# summing_circuit.net
KiCad netlist of a schematic drawn in Altium Designer
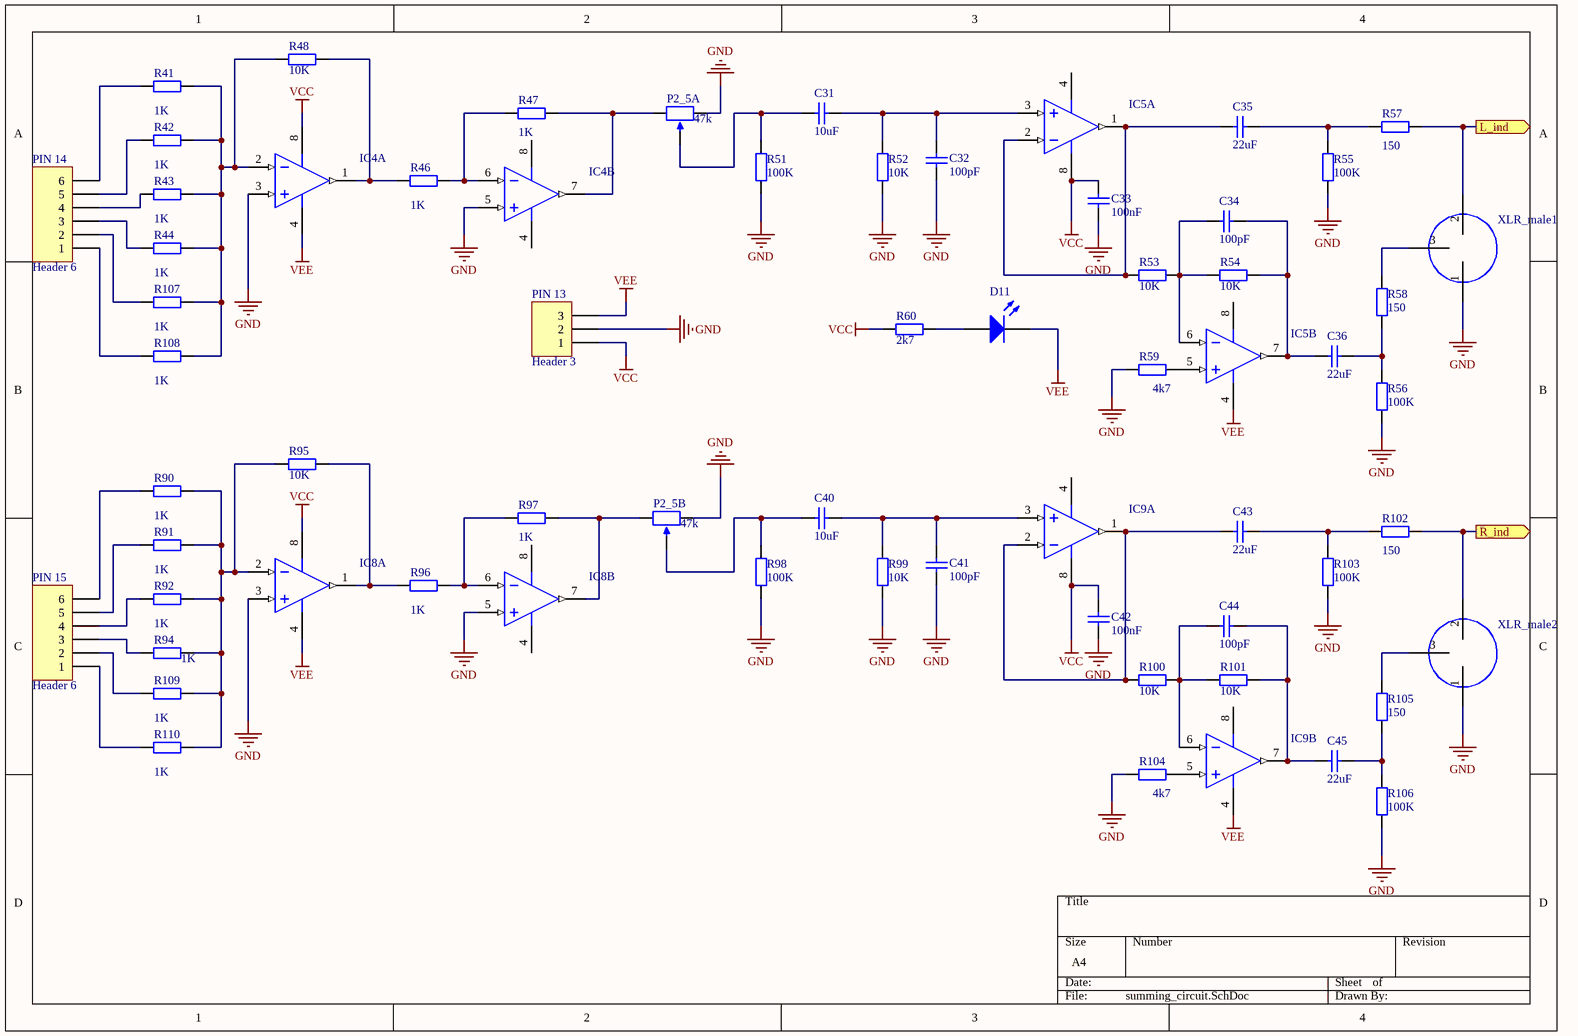
[diagram p0: summing_circuit.SchDoc]

(export (version "E")
  (design (tool "Eeschema 10.0.6"))
  (components
    (comp (ref "C31")
      (value "10uF")
      (footprint "Capacitor 10uF")
      (description "Capacitor")
      (fields (field (name "Comment") "Cap") (field (name "PUBLISHER") "Altium Limited"))
      (libsource (lib "Autio_Mixer") (part "Cap"))
    )
    (comp (ref "C32")
      (value "100pF")
      (footprint "Capacitor 100pF")
      (description "Capacitor")
      (fields (field (name "Comment") "Cap") (field (name "PUBLISHER") "Altium Limited"))
      (libsource (lib "Autio_Mixer") (part "Cap"))
    )
    (comp (ref "C33")
      (value "100nF")
      (footprint "Capacitor 22nF, 47nF, 100nF")
      (description "Capacitor")
      (fields (field (name "Comment") "Cap") (field (name "PUBLISHER") "Altium Limited"))
      (libsource (lib "Autio_Mixer") (part "Cap_3"))
    )
    (comp (ref "C34")
      (value "100pF")
      (footprint "Capacitor 100pF")
      (description "Capacitor")
      (fields (field (name "Comment") "Cap") (field (name "PUBLISHER") "Altium Limited"))
      (libsource (lib "Autio_Mixer") (part "Cap"))
    )
    (comp (ref "C35")
      (value "22uF")
      (footprint "Capacitor 100uF")
      (description "Capacitor")
      (fields (field (name "Comment") "Cap") (field (name "PUBLISHER") "Altium Limited"))
      (libsource (lib "Autio_Mixer") (part "Cap"))
    )
    (comp (ref "C36")
      (value "22uF")
      (footprint "Capacitor 100uF")
      (description "Capacitor")
      (fields (field (name "Comment") "Cap") (field (name "PUBLISHER") "Altium Limited"))
      (libsource (lib "Autio_Mixer") (part "Cap_5"))
    )
    (comp (ref "C40")
      (value "10uF")
      (footprint "Capacitor 10uF")
      (description "Capacitor")
      (fields (field (name "Comment") "Cap") (field (name "PUBLISHER") "Altium Limited"))
      (libsource (lib "Autio_Mixer") (part "Cap"))
    )
    (comp (ref "C41")
      (value "100pF")
      (footprint "Capacitor 100pF")
      (description "Capacitor")
      (fields (field (name "Comment") "Cap") (field (name "PUBLISHER") "Altium Limited"))
      (libsource (lib "Autio_Mixer") (part "Cap"))
    )
    (comp (ref "C42")
      (value "100nF")
      (footprint "Capacitor 22nF, 47nF, 100nF")
      (description "Capacitor")
      (fields (field (name "Comment") "Cap") (field (name "PUBLISHER") "Altium Limited"))
      (libsource (lib "Autio_Mixer") (part "Cap_3"))
    )
    (comp (ref "C43")
      (value "22uF")
      (footprint "Capacitor 100pF")
      (description "Capacitor")
      (fields (field (name "Comment") "Cap") (field (name "PUBLISHER") "Altium Limited"))
      (libsource (lib "Autio_Mixer") (part "Cap"))
    )
    (comp (ref "C44")
      (value "100pF")
      (footprint "Capacitor 100uF")
      (description "Capacitor")
      (fields (field (name "Comment") "Cap") (field (name "PUBLISHER") "Altium Limited"))
      (libsource (lib "Autio_Mixer") (part "Cap"))
    )
    (comp (ref "C45")
      (value "22uF")
      (footprint "Capacitor 100uF")
      (description "Capacitor")
      (fields (field (name "Comment") "Cap") (field (name "PUBLISHER") "Altium Limited"))
      (libsource (lib "Autio_Mixer") (part "Cap_5"))
    )
    (comp (ref "D11")
      (value "LED1")
      (footprint "LED")
      (description "Typical RED GaAs LED")
      (fields (field (name "PUBLISHER") "Altium Limited"))
      (libsource (lib "Autio_Mixer") (part "LED1"))
    )
    (comp (ref "IC4")
      (value "LM833DR2G")
      (footprint "OPAMP_LM833")
      (description "Low Noise, Audio Dual Operational Amplifier, -40 to 85 degC, 8-Pin SOIC, Pb-Free, Tape and Reel")
      (fields (field (name "MANUFACTURER") "On Semiconductor"))
      (libsource (lib "Autio_Mixer") (part "opamp_LM833"))
    )
    (comp (ref "IC5")
      (value "LM833DR2G")
      (footprint "OPAMP_LM833")
      (description "Low Noise, Audio Dual Operational Amplifier, -40 to 85 degC, 8-Pin SOIC, Pb-Free, Tape and Reel")
      (fields (field (name "MANUFACTURER") "On Semiconductor"))
      (libsource (lib "Autio_Mixer") (part "opamp_LM833"))
    )
    (comp (ref "IC8")
      (value "LM833DR2G")
      (footprint "OPAMP_LM833")
      (description "Low Noise, Audio Dual Operational Amplifier, -40 to 85 degC, 8-Pin SOIC, Pb-Free, Tape and Reel")
      (fields (field (name "MANUFACTURER") "On Semiconductor"))
      (libsource (lib "Autio_Mixer") (part "opamp_LM833"))
    )
    (comp (ref "IC9")
      (value "LM833DR2G")
      (footprint "OPAMP_LM833")
      (description "Low Noise, Audio Dual Operational Amplifier, -40 to 85 degC, 8-Pin SOIC, Pb-Free, Tape and Reel")
      (fields (field (name "MANUFACTURER") "On Semiconductor"))
      (libsource (lib "Autio_Mixer") (part "opamp_LM833"))
    )
    (comp (ref "P2_5A")
      (value "47k")
      (footprint "header_3")
      (description "Potentiometer")
      (fields (field (name "Comment") "RPot") (field (name "PUBLISHER") "Altium Limited"))
      (libsource (lib "Autio_Mixer") (part "RPot"))
    )
    (comp (ref "P2_5B")
      (value "47k")
      (footprint "header_3")
      (description "Potentiometer")
      (fields (field (name "Comment") "RPot") (field (name "PUBLISHER") "Altium Limited"))
      (libsource (lib "Autio_Mixer") (part "RPot"))
    )
    (comp (ref "PIN 13")
      (value "Header 3")
      (footprint "header_3")
      (description "Header, 3-Pin")
      (fields (field (name "PUBLISHER") "Altium Limited"))
      (libsource (lib "Miscellaneous Connectors") (part "Header 3"))
    )
    (comp (ref "PIN 14")
      (value "Header 6")
      (footprint "header_6")
      (description "Header, 6-Pin")
      (fields (field (name "PUBLISHER") "Altium Limited"))
      (libsource (lib "Miscellaneous Connectors") (part "Header 6"))
    )
    (comp (ref "PIN 15")
      (value "Header 6")
      (footprint "header_6")
      (description "Header, 6-Pin")
      (fields (field (name "PUBLISHER") "Altium Limited"))
      (libsource (lib "Miscellaneous Connectors") (part "Header 6"))
    )
    (comp (ref "R41")
      (value "1K")
      (footprint "C1206")
      (description "Resistor")
      (fields (field (name "Comment") "Res2") (field (name "PUBLISHER") "Altium Limited"))
      (libsource (lib "Miscellaneous Devices") (part "Res2"))
    )
    (comp (ref "R42")
      (value "1K")
      (footprint "C1206")
      (description "Resistor")
      (fields (field (name "Comment") "Res2") (field (name "PUBLISHER") "Altium Limited"))
      (libsource (lib "Miscellaneous Devices") (part "Res2"))
    )
    (comp (ref "R43")
      (value "1K")
      (footprint "C1206")
      (description "Resistor")
      (fields (field (name "Comment") "Res2") (field (name "PUBLISHER") "Altium Limited"))
      (libsource (lib "Miscellaneous Devices") (part "Res2"))
    )
    (comp (ref "R44")
      (value "1K")
      (footprint "C1206")
      (description "Resistor")
      (fields (field (name "Comment") "Res2") (field (name "PUBLISHER") "Altium Limited"))
      (libsource (lib "Miscellaneous Devices") (part "Res2"))
    )
    (comp (ref "R46")
      (value "1K")
      (footprint "C1206")
      (description "Resistor")
      (fields (field (name "Comment") "Res2") (field (name "PUBLISHER") "Altium Limited"))
      (libsource (lib "Miscellaneous Devices") (part "Res2"))
    )
    (comp (ref "R47")
      (value "1K")
      (footprint "C1206")
      (description "Resistor")
      (fields (field (name "Comment") "Res2") (field (name "PUBLISHER") "Altium Limited"))
      (libsource (lib "Miscellaneous Devices") (part "Res2"))
    )
    (comp (ref "R48")
      (value "10K")
      (footprint "C1206")
      (description "Resistor")
      (fields (field (name "Comment") "Res2") (field (name "PUBLISHER") "Altium Limited"))
      (libsource (lib "Autio_Mixer") (part "Res2_3"))
    )
    (comp (ref "R51")
      (value "100K")
      (footprint "C1206")
      (description "Resistor")
      (fields (field (name "Comment") "Res2") (field (name "PUBLISHER") "Altium Limited"))
      (libsource (lib "Autio_Mixer") (part "Res2_5"))
    )
    (comp (ref "R52")
      (value "10K")
      (footprint "C1206")
      (description "Resistor")
      (fields (field (name "Comment") "Res2") (field (name "PUBLISHER") "Altium Limited"))
      (libsource (lib "") (part "Res2_3_1"))
    )
    (comp (ref "R53")
      (value "10K")
      (footprint "C1206")
      (description "Resistor")
      (fields (field (name "Comment") "Res2") (field (name "PUBLISHER") "Altium Limited"))
      (libsource (lib "Autio_Mixer") (part "Res2_3"))
    )
    (comp (ref "R54")
      (value "10K")
      (footprint "C1206")
      (description "Resistor")
      (fields (field (name "Comment") "Res2") (field (name "PUBLISHER") "Altium Limited"))
      (libsource (lib "Autio_Mixer") (part "Res2_3"))
    )
    (comp (ref "R55")
      (value "100K")
      (footprint "C1206")
      (description "Resistor")
      (fields (field (name "Comment") "Res2") (field (name "PUBLISHER") "Altium Limited"))
      (libsource (lib "Autio_Mixer") (part "Res2_5"))
    )
    (comp (ref "R56")
      (value "100K")
      (footprint "C1206")
      (description "Resistor")
      (fields (field (name "Comment") "Res2") (field (name "PUBLISHER") "Altium Limited"))
      (libsource (lib "Autio_Mixer") (part "Res2_5"))
    )
    (comp (ref "R57")
      (value "150")
      (footprint "C1206")
      (description "Resistor")
      (fields (field (name "Comment") "Res2") (field (name "PUBLISHER") "Altium Limited"))
      (libsource (lib "Miscellaneous Devices") (part "Res2"))
    )
    (comp (ref "R58")
      (value "150")
      (footprint "C1206")
      (description "Resistor")
      (fields (field (name "Comment") "Res2") (field (name "PUBLISHER") "Altium Limited"))
      (libsource (lib "") (part "Res2_1"))
    )
    (comp (ref "R59")
      (value "4k7")
      (footprint "C1206")
      (description "Resistor")
      (fields (field (name "Comment") "Res2") (field (name "PUBLISHER") "Altium Limited"))
      (libsource (lib "Miscellaneous Devices") (part "Res2"))
    )
    (comp (ref "R60")
      (value "2k7")
      (footprint "C1206")
      (description "Resistor")
      (fields (field (name "Comment") "Res2") (field (name "PUBLISHER") "Altium Limited"))
      (libsource (lib "Autio_Mixer") (part "Res_16"))
    )
    (comp (ref "R90")
      (value "1K")
      (footprint "C1206")
      (description "Resistor")
      (fields (field (name "Comment") "Res2") (field (name "PUBLISHER") "Altium Limited"))
      (libsource (lib "Miscellaneous Devices") (part "Res2"))
    )
    (comp (ref "R91")
      (value "1K")
      (footprint "C1206")
      (description "Resistor")
      (fields (field (name "Comment") "Res2") (field (name "PUBLISHER") "Altium Limited"))
      (libsource (lib "Miscellaneous Devices") (part "Res2"))
    )
    (comp (ref "R92")
      (value "1K")
      (footprint "C1206")
      (description "Resistor")
      (fields (field (name "Comment") "Res2") (field (name "PUBLISHER") "Altium Limited"))
      (libsource (lib "Miscellaneous Devices") (part "Res2"))
    )
    (comp (ref "R94")
      (value "1K")
      (footprint "C1206")
      (description "Resistor")
      (fields (field (name "Comment") "Res2") (field (name "PUBLISHER") "Altium Limited"))
      (libsource (lib "Miscellaneous Devices") (part "Res2"))
    )
    (comp (ref "R95")
      (value "10K")
      (footprint "C1206")
      (description "Resistor")
      (fields (field (name "Comment") "Res2") (field (name "PUBLISHER") "Altium Limited"))
      (libsource (lib "Autio_Mixer") (part "Res2_3"))
    )
    (comp (ref "R96")
      (value "1K")
      (footprint "C1206")
      (description "Resistor")
      (fields (field (name "Comment") "Res2") (field (name "PUBLISHER") "Altium Limited"))
      (libsource (lib "Miscellaneous Devices") (part "Res2"))
    )
    (comp (ref "R97")
      (value "1K")
      (footprint "C1206")
      (description "Resistor")
      (fields (field (name "Comment") "Res2") (field (name "PUBLISHER") "Altium Limited"))
      (libsource (lib "Miscellaneous Devices") (part "Res2"))
    )
    (comp (ref "R98")
      (value "100K")
      (footprint "C1206")
      (description "Resistor")
      (fields (field (name "Comment") "Res2") (field (name "PUBLISHER") "Altium Limited"))
      (libsource (lib "Autio_Mixer") (part "Res2_5"))
    )
    (comp (ref "R99")
      (value "10K")
      (footprint "C1206")
      (description "Resistor")
      (fields (field (name "Comment") "Res2") (field (name "PUBLISHER") "Altium Limited"))
      (libsource (lib "") (part "Res2_3_1"))
    )
    (comp (ref "R100")
      (value "10K")
      (footprint "C1206")
      (description "Resistor")
      (fields (field (name "Comment") "Res2") (field (name "PUBLISHER") "Altium Limited"))
      (libsource (lib "Autio_Mixer") (part "Res2_3"))
    )
    (comp (ref "R101")
      (value "10K")
      (footprint "C1206")
      (description "Resistor")
      (fields (field (name "Comment") "Res2") (field (name "PUBLISHER") "Altium Limited"))
      (libsource (lib "Autio_Mixer") (part "Res2_3"))
    )
    (comp (ref "R102")
      (value "150")
      (footprint "C1206")
      (description "Resistor")
      (fields (field (name "Comment") "Res2") (field (name "PUBLISHER") "Altium Limited"))
      (libsource (lib "Miscellaneous Devices") (part "Res2"))
    )
    (comp (ref "R103")
      (value "100K")
      (footprint "C1206")
      (description "Resistor")
      (fields (field (name "Comment") "Res2") (field (name "PUBLISHER") "Altium Limited"))
      (libsource (lib "Autio_Mixer") (part "Res2_5"))
    )
    (comp (ref "R104")
      (value "4k7")
      (footprint "C1206")
      (description "Resistor")
      (fields (field (name "Comment") "Res2") (field (name "PUBLISHER") "Altium Limited"))
      (libsource (lib "Miscellaneous Devices") (part "Res2"))
    )
    (comp (ref "R105")
      (value "150")
      (footprint "C1206")
      (description "Resistor")
      (fields (field (name "Comment") "Res2") (field (name "PUBLISHER") "Altium Limited"))
      (libsource (lib "") (part "Res2_1"))
    )
    (comp (ref "R106")
      (value "100K")
      (footprint "C1206")
      (description "Resistor")
      (fields (field (name "Comment") "Res2") (field (name "PUBLISHER") "Altium Limited"))
      (libsource (lib "Autio_Mixer") (part "Res2_5"))
    )
    (comp (ref "R107")
      (value "1K")
      (footprint "C1206")
      (description "Resistor")
      (fields (field (name "Comment") "Res2") (field (name "PUBLISHER") "Altium Limited"))
      (libsource (lib "Miscellaneous Devices") (part "Res2"))
    )
    (comp (ref "R108")
      (value "1K")
      (footprint "C1206")
      (description "Resistor")
      (fields (field (name "Comment") "Res2") (field (name "PUBLISHER") "Altium Limited"))
      (libsource (lib "Miscellaneous Devices") (part "Res2"))
    )
    (comp (ref "R109")
      (value "1K")
      (footprint "C1206")
      (description "Resistor")
      (fields (field (name "Comment") "Res2") (field (name "PUBLISHER") "Altium Limited"))
      (libsource (lib "Miscellaneous Devices") (part "Res2"))
    )
    (comp (ref "R110")
      (value "1K")
      (footprint "C1206")
      (description "Resistor")
      (fields (field (name "Comment") "Res2") (field (name "PUBLISHER") "Altium Limited"))
      (libsource (lib "Miscellaneous Devices") (part "Res2"))
    )
    (comp (ref "XLR_male1")
      (value "XLR_male")
      (footprint "XLR_MALE_Neutrik_NC3_MAV")
      (libsource (lib "Autio_Mixer") (part "XLR_male"))
    )
    (comp (ref "XLR_male2")
      (value "XLR_male")
      (footprint "XLR_MALE_Neutrik_NC3_MAV")
      (libsource (lib "Autio_Mixer") (part "XLR_male"))
    )
  )
  (nets
    (net (code "1") (name "/L_ind") (class "Default")
      (node (ref "R57") (pin "2") (pinfunction "2_2") (pintype "passive"))
      (node (ref "XLR_male1") (pin "2") (pinfunction "Pos_2") (pintype "passive"))
    )
    (net (code "2") (name "/R_ind") (class "Default")
      (node (ref "R102") (pin "2") (pinfunction "2_2") (pintype "passive"))
      (node (ref "XLR_male2") (pin "2") (pinfunction "Pos_2") (pintype "passive"))
    )
    (net (code "3") (name "GND") (class "Default")
      (node (ref "C32") (pin "1") (pinfunction "1_1") (pintype "passive"))
      (node (ref "C33") (pin "1") (pinfunction "1_1") (pintype "passive"))
      (node (ref "C41") (pin "1") (pinfunction "1_1") (pintype "passive"))
      (node (ref "C42") (pin "1") (pinfunction "1_1") (pintype "passive"))
      (node (ref "IC4") (pin "3") (pinfunction "IN1+_3") (pintype "input"))
      (node (ref "IC4") (pin "5") (pinfunction "IN2+_5") (pintype "input"))
      (node (ref "IC8") (pin "3") (pinfunction "IN1+_3") (pintype "input"))
      (node (ref "IC8") (pin "5") (pinfunction "IN2+_5") (pintype "input"))
      (node (ref "P2_5A") (pin "3") (pinfunction "BOT_3") (pintype "passive"))
      (node (ref "P2_5B") (pin "3") (pinfunction "BOT_3") (pintype "passive"))
      (node (ref "PIN 13") (pin "1") (pinfunction "2_1") (pintype "passive"))
      (node (ref "R103") (pin "1") (pinfunction "1_1") (pintype "passive"))
      (node (ref "R104") (pin "1") (pinfunction "1_1") (pintype "passive"))
      (node (ref "R106") (pin "1") (pinfunction "1_1") (pintype "passive"))
      (node (ref "R51") (pin "1") (pinfunction "1_1") (pintype "passive"))
      (node (ref "R52") (pin "1") (pinfunction "1_1") (pintype "passive"))
      (node (ref "R55") (pin "1") (pinfunction "1_1") (pintype "passive"))
      (node (ref "R56") (pin "1") (pinfunction "1_1") (pintype "passive"))
      (node (ref "R59") (pin "1") (pinfunction "1_1") (pintype "passive"))
      (node (ref "R98") (pin "1") (pinfunction "1_1") (pintype "passive"))
      (node (ref "R99") (pin "1") (pinfunction "1_1") (pintype "passive"))
      (node (ref "XLR_male1") (pin "1") (pinfunction "GND_1") (pintype "passive"))
      (node (ref "XLR_male2") (pin "1") (pinfunction "GND_1") (pintype "passive"))
    )
    (net (code "4") (name "Net-(C35-Pad2)") (class "Default")
      (node (ref "C35") (pin "2") (pinfunction "2_2") (pintype "passive"))
      (node (ref "R55") (pin "2") (pinfunction "2_2") (pintype "passive"))
      (node (ref "R57") (pin "1") (pinfunction "1_1") (pintype "passive"))
    )
    (net (code "5") (name "Net-(C36-Pad2)") (class "Default")
      (node (ref "C36") (pin "2") (pinfunction "2_2") (pintype "passive"))
      (node (ref "R56") (pin "2") (pinfunction "2_2") (pintype "passive"))
      (node (ref "R58") (pin "1") (pinfunction "1_1") (pintype "passive"))
    )
    (net (code "6") (name "Net-(C43-Pad2)") (class "Default")
      (node (ref "C43") (pin "2") (pinfunction "2_2") (pintype "passive"))
      (node (ref "R102") (pin "1") (pinfunction "1_1") (pintype "passive"))
      (node (ref "R103") (pin "2") (pinfunction "2_2") (pintype "passive"))
    )
    (net (code "7") (name "Net-(C45-Pad2)") (class "Default")
      (node (ref "C45") (pin "2") (pinfunction "2_2") (pintype "passive"))
      (node (ref "R105") (pin "1") (pinfunction "1_1") (pintype "passive"))
      (node (ref "R106") (pin "2") (pinfunction "2_2") (pintype "passive"))
    )
    (net (code "8") (name "Net-(D11-A)") (class "Default")
      (node (ref "D11") (pin "1") (pinfunction "A_1") (pintype "passive"))
      (node (ref "R60") (pin "2") (pinfunction "2_2") (pintype "passive"))
    )
    (net (code "9") (name "Net-(IC4A-IN1-)") (class "Default")
      (node (ref "IC4") (pin "2") (pinfunction "IN1-_2") (pintype "input"))
      (node (ref "R107") (pin "2") (pinfunction "2_2") (pintype "passive"))
      (node (ref "R108") (pin "2") (pinfunction "2_2") (pintype "passive"))
      (node (ref "R41") (pin "2") (pinfunction "2_2") (pintype "passive"))
      (node (ref "R42") (pin "2") (pinfunction "2_2") (pintype "passive"))
      (node (ref "R43") (pin "2") (pinfunction "2_2") (pintype "passive"))
      (node (ref "R44") (pin "2") (pinfunction "2_2") (pintype "passive"))
      (node (ref "R48") (pin "1") (pinfunction "1_1") (pintype "passive"))
    )
    (net (code "10") (name "Net-(IC4A-OUT1)") (class "Default")
      (node (ref "IC4") (pin "1") (pinfunction "OUT1_1") (pintype "output"))
      (node (ref "R46") (pin "1") (pinfunction "1_1") (pintype "passive"))
      (node (ref "R48") (pin "2") (pinfunction "2_2") (pintype "passive"))
    )
    (net (code "11") (name "Net-(IC4B-IN2-)") (class "Default")
      (node (ref "IC4") (pin "6") (pinfunction "IN2-_6") (pintype "input"))
      (node (ref "R46") (pin "2") (pinfunction "2_2") (pintype "passive"))
      (node (ref "R47") (pin "1") (pinfunction "1_1") (pintype "passive"))
    )
    (net (code "12") (name "Net-(IC4B-OUT2)") (class "Default")
      (node (ref "IC4") (pin "7") (pinfunction "OUT2_7") (pintype "output"))
      (node (ref "P2_5A") (pin "1") (pinfunction "TOP_1") (pintype "passive"))
      (node (ref "R47") (pin "2") (pinfunction "2_2") (pintype "passive"))
    )
    (net (code "13") (name "Net-(IC5A-IN1+)") (class "Default")
      (node (ref "C31") (pin "2") (pinfunction "2_2") (pintype "passive"))
      (node (ref "C32") (pin "2") (pinfunction "2_2") (pintype "passive"))
      (node (ref "IC5") (pin "3") (pinfunction "IN1+_3") (pintype "input"))
      (node (ref "R52") (pin "2") (pinfunction "2_2") (pintype "passive"))
    )
    (net (code "14") (name "Net-(IC5A-IN1-)") (class "Default")
      (node (ref "C35") (pin "1") (pinfunction "1_1") (pintype "passive"))
      (node (ref "IC5") (pin "1") (pinfunction "OUT1_1") (pintype "output"))
      (node (ref "IC5") (pin "2") (pinfunction "IN1-_2") (pintype "input"))
      (node (ref "R53") (pin "1") (pinfunction "1_1") (pintype "passive"))
    )
    (net (code "15") (name "Net-(IC5B-IN2+)") (class "Default")
      (node (ref "IC5") (pin "5") (pinfunction "IN2+_5") (pintype "input"))
      (node (ref "R59") (pin "2") (pinfunction "2_2") (pintype "passive"))
    )
    (net (code "16") (name "Net-(IC5B-IN2-)") (class "Default")
      (node (ref "C34") (pin "1") (pinfunction "1_1") (pintype "passive"))
      (node (ref "IC5") (pin "6") (pinfunction "IN2-_6") (pintype "input"))
      (node (ref "R53") (pin "2") (pinfunction "2_2") (pintype "passive"))
      (node (ref "R54") (pin "1") (pinfunction "1_1") (pintype "passive"))
    )
    (net (code "17") (name "Net-(IC5B-OUT2)") (class "Default")
      (node (ref "C34") (pin "2") (pinfunction "2_2") (pintype "passive"))
      (node (ref "C36") (pin "1") (pinfunction "1_1") (pintype "passive"))
      (node (ref "IC5") (pin "7") (pinfunction "OUT2_7") (pintype "output"))
      (node (ref "R54") (pin "2") (pinfunction "2_2") (pintype "passive"))
    )
    (net (code "18") (name "Net-(IC8A-IN1-)") (class "Default")
      (node (ref "IC8") (pin "2") (pinfunction "IN1-_2") (pintype "input"))
      (node (ref "R109") (pin "2") (pinfunction "2_2") (pintype "passive"))
      (node (ref "R110") (pin "2") (pinfunction "2_2") (pintype "passive"))
      (node (ref "R90") (pin "2") (pinfunction "2_2") (pintype "passive"))
      (node (ref "R91") (pin "2") (pinfunction "2_2") (pintype "passive"))
      (node (ref "R92") (pin "2") (pinfunction "2_2") (pintype "passive"))
      (node (ref "R94") (pin "2") (pinfunction "2_2") (pintype "passive"))
      (node (ref "R95") (pin "1") (pinfunction "1_1") (pintype "passive"))
    )
    (net (code "19") (name "Net-(IC8A-OUT1)") (class "Default")
      (node (ref "IC8") (pin "1") (pinfunction "OUT1_1") (pintype "output"))
      (node (ref "R95") (pin "2") (pinfunction "2_2") (pintype "passive"))
      (node (ref "R96") (pin "1") (pinfunction "1_1") (pintype "passive"))
    )
    (net (code "20") (name "Net-(IC8B-IN2-)") (class "Default")
      (node (ref "IC8") (pin "6") (pinfunction "IN2-_6") (pintype "input"))
      (node (ref "R96") (pin "2") (pinfunction "2_2") (pintype "passive"))
      (node (ref "R97") (pin "1") (pinfunction "1_1") (pintype "passive"))
    )
    (net (code "21") (name "Net-(IC8B-OUT2)") (class "Default")
      (node (ref "IC8") (pin "7") (pinfunction "OUT2_7") (pintype "output"))
      (node (ref "P2_5B") (pin "1") (pinfunction "TOP_1") (pintype "passive"))
      (node (ref "R97") (pin "2") (pinfunction "2_2") (pintype "passive"))
    )
    (net (code "22") (name "Net-(IC9A-IN1+)") (class "Default")
      (node (ref "C40") (pin "2") (pinfunction "2_2") (pintype "passive"))
      (node (ref "C41") (pin "2") (pinfunction "2_2") (pintype "passive"))
      (node (ref "IC9") (pin "3") (pinfunction "IN1+_3") (pintype "input"))
      (node (ref "R99") (pin "2") (pinfunction "2_2") (pintype "passive"))
    )
    (net (code "23") (name "Net-(IC9A-IN1-)") (class "Default")
      (node (ref "C43") (pin "1") (pinfunction "1_1") (pintype "passive"))
      (node (ref "IC9") (pin "1") (pinfunction "OUT1_1") (pintype "output"))
      (node (ref "IC9") (pin "2") (pinfunction "IN1-_2") (pintype "input"))
      (node (ref "R100") (pin "1") (pinfunction "1_1") (pintype "passive"))
    )
    (net (code "24") (name "Net-(IC9B-IN2+)") (class "Default")
      (node (ref "IC9") (pin "5") (pinfunction "IN2+_5") (pintype "input"))
      (node (ref "R104") (pin "2") (pinfunction "2_2") (pintype "passive"))
    )
    (net (code "25") (name "Net-(IC9B-IN2-)") (class "Default")
      (node (ref "C44") (pin "1") (pinfunction "1_1") (pintype "passive"))
      (node (ref "IC9") (pin "6") (pinfunction "IN2-_6") (pintype "input"))
      (node (ref "R100") (pin "2") (pinfunction "2_2") (pintype "passive"))
      (node (ref "R101") (pin "1") (pinfunction "1_1") (pintype "passive"))
    )
    (net (code "26") (name "Net-(IC9B-OUT2)") (class "Default")
      (node (ref "C44") (pin "2") (pinfunction "2_2") (pintype "passive"))
      (node (ref "C45") (pin "1") (pinfunction "1_1") (pintype "passive"))
      (node (ref "IC9") (pin "7") (pinfunction "OUT2_7") (pintype "output"))
      (node (ref "R101") (pin "2") (pinfunction "2_2") (pintype "passive"))
    )
    (net (code "27") (name "Net-(P2_5A-TAP)") (class "Default")
      (node (ref "C31") (pin "1") (pinfunction "1_1") (pintype "passive"))
      (node (ref "P2_5A") (pin "2") (pinfunction "TAP_2") (pintype "passive"))
      (node (ref "R51") (pin "2") (pinfunction "2_2") (pintype "passive"))
    )
    (net (code "28") (name "Net-(P2_5B-TAP)") (class "Default")
      (node (ref "C40") (pin "1") (pinfunction "1_1") (pintype "passive"))
      (node (ref "P2_5B") (pin "2") (pinfunction "TAP_2") (pintype "passive"))
      (node (ref "R98") (pin "2") (pinfunction "2_2") (pintype "passive"))
    )
    (net (code "29") (name "Net-(PIN 14-1)") (class "Default")
      (node (ref "PIN 14") (pin "2") (pinfunction "1_2") (pintype "passive"))
      (node (ref "R108") (pin "1") (pinfunction "1_1") (pintype "passive"))
    )
    (net (code "30") (name "Net-(PIN 14-2)") (class "Default")
      (node (ref "PIN 14") (pin "1") (pinfunction "2_1") (pintype "passive"))
      (node (ref "R107") (pin "1") (pinfunction "1_1") (pintype "passive"))
    )
    (net (code "31") (name "Net-(PIN 14-Pad3)") (class "Default")
      (node (ref "PIN 14") (pin "3") (pinfunction "3_3") (pintype "passive"))
      (node (ref "R44") (pin "1") (pinfunction "1_1") (pintype "passive"))
    )
    (net (code "32") (name "Net-(PIN 14-Pad4)") (class "Default")
      (node (ref "PIN 14") (pin "4") (pinfunction "4_4") (pintype "passive"))
      (node (ref "R43") (pin "1") (pinfunction "1_1") (pintype "passive"))
    )
    (net (code "33") (name "Net-(PIN 14-Pad5)") (class "Default")
      (node (ref "PIN 14") (pin "5") (pinfunction "5_5") (pintype "passive"))
      (node (ref "R42") (pin "1") (pinfunction "1_1") (pintype "passive"))
    )
    (net (code "34") (name "Net-(PIN 14-Pad6)") (class "Default")
      (node (ref "PIN 14") (pin "6") (pinfunction "6_6") (pintype "passive"))
      (node (ref "R41") (pin "1") (pinfunction "1_1") (pintype "passive"))
    )
    (net (code "35") (name "Net-(PIN 15-1)") (class "Default")
      (node (ref "PIN 15") (pin "2") (pinfunction "1_2") (pintype "passive"))
      (node (ref "R110") (pin "1") (pinfunction "1_1") (pintype "passive"))
    )
    (net (code "36") (name "Net-(PIN 15-2)") (class "Default")
      (node (ref "PIN 15") (pin "1") (pinfunction "2_1") (pintype "passive"))
      (node (ref "R109") (pin "1") (pinfunction "1_1") (pintype "passive"))
    )
    (net (code "37") (name "Net-(PIN 15-Pad3)") (class "Default")
      (node (ref "PIN 15") (pin "3") (pinfunction "3_3") (pintype "passive"))
      (node (ref "R94") (pin "1") (pinfunction "1_1") (pintype "passive"))
    )
    (net (code "38") (name "Net-(PIN 15-Pad4)") (class "Default")
      (node (ref "PIN 15") (pin "4") (pinfunction "4_4") (pintype "passive"))
      (node (ref "R92") (pin "1") (pinfunction "1_1") (pintype "passive"))
    )
    (net (code "39") (name "Net-(PIN 15-Pad5)") (class "Default")
      (node (ref "PIN 15") (pin "5") (pinfunction "5_5") (pintype "passive"))
      (node (ref "R91") (pin "1") (pinfunction "1_1") (pintype "passive"))
    )
    (net (code "40") (name "Net-(PIN 15-Pad6)") (class "Default")
      (node (ref "PIN 15") (pin "6") (pinfunction "6_6") (pintype "passive"))
      (node (ref "R90") (pin "1") (pinfunction "1_1") (pintype "passive"))
    )
    (net (code "41") (name "Net-(XLR_male1-negative)") (class "Default")
      (node (ref "R58") (pin "2") (pinfunction "2_2") (pintype "passive"))
      (node (ref "XLR_male1") (pin "3") (pinfunction "negative_3") (pintype "passive"))
    )
    (net (code "42") (name "Net-(XLR_male2-negative)") (class "Default")
      (node (ref "R105") (pin "2") (pinfunction "2_2") (pintype "passive"))
      (node (ref "XLR_male2") (pin "3") (pinfunction "negative_3") (pintype "passive"))
    )
    (net (code "43") (name "VCC") (class "Default")
      (node (ref "C33") (pin "2") (pinfunction "2_2") (pintype "passive"))
      (node (ref "C42") (pin "2") (pinfunction "2_2") (pintype "passive"))
      (node (ref "IC4") (pin "8") (pinfunction "VCC_8") (pintype "power_in"))
      (node (ref "IC5") (pin "8") (pinfunction "VCC_8") (pintype "power_in"))
      (node (ref "IC8") (pin "8") (pinfunction "VCC_8") (pintype "power_in"))
      (node (ref "IC9") (pin "8") (pinfunction "VCC_8") (pintype "power_in"))
      (node (ref "PIN 13") (pin "2") (pinfunction "1_2") (pintype "passive"))
      (node (ref "R60") (pin "1") (pinfunction "1_1") (pintype "passive"))
    )
    (net (code "44") (name "VEE") (class "Default")
      (node (ref "D11") (pin "2") (pinfunction "K_2") (pintype "passive"))
      (node (ref "IC4") (pin "4") (pinfunction "VEE_4") (pintype "power_in"))
      (node (ref "IC5") (pin "4") (pinfunction "VEE_4") (pintype "power_in"))
      (node (ref "IC8") (pin "4") (pinfunction "VEE_4") (pintype "power_in"))
      (node (ref "IC9") (pin "4") (pinfunction "VEE_4") (pintype "power_in"))
      (node (ref "PIN 13") (pin "3") (pinfunction "3_3") (pintype "passive"))
    )
    (net (code "45") (name "unconnected-(IC4B-VCC-Pad8)") (class "Default")
      (node (ref "IC4") (pin "8") (pinfunction "VCC_8") (pintype "power_in"))
    )
    (net (code "46") (name "unconnected-(IC4B-VEE-Pad4)") (class "Default")
      (node (ref "IC4") (pin "4") (pinfunction "VEE_4") (pintype "power_in"))
    )
    (net (code "47") (name "unconnected-(IC5A-VEE-Pad4)") (class "Default")
      (node (ref "IC5") (pin "4") (pinfunction "VEE_4") (pintype "power_in"))
    )
    (net (code "48") (name "unconnected-(IC5B-VCC-Pad8)") (class "Default")
      (node (ref "IC5") (pin "8") (pinfunction "VCC_8") (pintype "power_in"))
    )
    (net (code "49") (name "unconnected-(IC8B-VCC-Pad8)") (class "Default")
      (node (ref "IC8") (pin "8") (pinfunction "VCC_8") (pintype "power_in"))
    )
    (net (code "50") (name "unconnected-(IC8B-VEE-Pad4)") (class "Default")
      (node (ref "IC8") (pin "4") (pinfunction "VEE_4") (pintype "power_in"))
    )
    (net (code "51") (name "unconnected-(IC9A-VEE-Pad4)") (class "Default")
      (node (ref "IC9") (pin "4") (pinfunction "VEE_4") (pintype "power_in"))
    )
    (net (code "52") (name "unconnected-(IC9B-VCC-Pad8)") (class "Default")
      (node (ref "IC9") (pin "8") (pinfunction "VCC_8") (pintype "power_in"))
    )
  )
)
